# at2313_isp_adapter.net
KiCad netlist of a schematic drawn in EAGLE
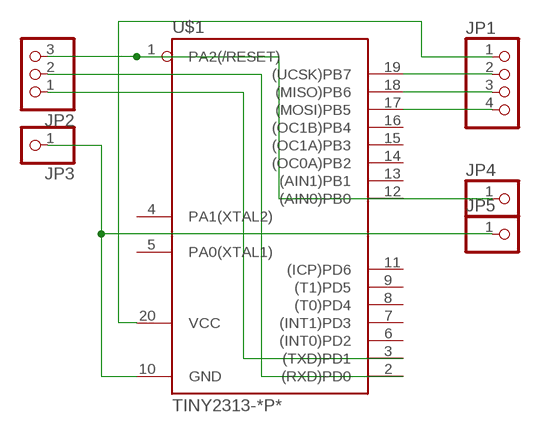
[diagram p0: schematic, sheet 1]

(export (version "E")
  (design (tool "Eeschema 10.0.6"))
  (components
    (comp (ref "JP1")
      (value "PINHD-1X4")
      (footprint "eagle-import:1X04")
      (libsource (lib "eagle-import") (part "PINHD-1X4"))
    )
    (comp (ref "JP2")
      (value "PINHD-1X3")
      (footprint "eagle-import:1X03")
      (libsource (lib "eagle-import") (part "PINHD-1X3"))
    )
    (comp (ref "JP3")
      (value "PINHD-1X1")
      (footprint "eagle-import:1X01")
      (libsource (lib "eagle-import") (part "PINHD-1X1"))
    )
    (comp (ref "JP4")
      (value "PINHD-1X1")
      (footprint "eagle-import:1X01")
      (libsource (lib "eagle-import") (part "PINHD-1X1"))
    )
    (comp (ref "JP5")
      (value "PINHD-1X1")
      (footprint "eagle-import:1X01")
      (libsource (lib "eagle-import") (part "PINHD-1X1"))
    )
    (comp (ref "U$1")
      (value "TINY2313-*P*")
      (footprint "eagle-import:DIL20")
      (libsource (lib "eagle-import") (part "TINY2313-P"))
    )
  )
  (nets
    (net (code "1") (name "Net-(U$1-(MISO)PB6)") (class "Default")
      (node (ref "JP1") (pin "3") (pinfunction "3_3") (pintype "passive"))
      (node (ref "U$1") (pin "18") (pinfunction "(MISO)PB6_18") (pintype "bidirectional"))
    )
    (net (code "2") (name "Net-(U$1-(MOSI)PB5)") (class "Default")
      (node (ref "JP1") (pin "4") (pinfunction "4_4") (pintype "passive"))
      (node (ref "U$1") (pin "17") (pinfunction "(MOSI)PB5_17") (pintype "bidirectional"))
    )
    (net (code "3") (name "Net-(U$1-(RXD)PD0)") (class "Default")
      (node (ref "JP2") (pin "2") (pinfunction "2_2") (pintype "passive"))
      (node (ref "U$1") (pin "2") (pinfunction "(RXD)PD0_2") (pintype "bidirectional"))
    )
    (net (code "4") (name "Net-(U$1-(TXD)PD1)") (class "Default")
      (node (ref "JP2") (pin "1") (pinfunction "1_1") (pintype "passive"))
      (node (ref "U$1") (pin "3") (pinfunction "(TXD)PD1_3") (pintype "bidirectional"))
    )
    (net (code "5") (name "Net-(U$1-(UCSK)PB7)") (class "Default")
      (node (ref "JP1") (pin "2") (pinfunction "2_2") (pintype "passive"))
      (node (ref "U$1") (pin "19") (pinfunction "(UCSK)PB7_19") (pintype "bidirectional"))
    )
    (net (code "6") (name "Net-(U$1-GND)") (class "Default")
      (node (ref "JP3") (pin "1") (pinfunction "1_1") (pintype "passive"))
      (node (ref "JP5") (pin "1") (pinfunction "1_1") (pintype "passive"))
      (node (ref "U$1") (pin "10") (pinfunction "GND_10") (pintype "power_in"))
    )
    (net (code "7") (name "Net-(U$1-PA2({slash}RESET))") (class "Default")
      (node (ref "JP2") (pin "3") (pinfunction "3_3") (pintype "passive"))
      (node (ref "JP4") (pin "1") (pinfunction "1_1") (pintype "passive"))
      (node (ref "U$1") (pin "1") (pinfunction "PA2(/RESET)_1") (pintype "input"))
    )
    (net (code "8") (name "Net-(U$1-VCC)") (class "Default")
      (node (ref "JP1") (pin "1") (pinfunction "1_1") (pintype "passive"))
      (node (ref "U$1") (pin "20") (pinfunction "VCC_20") (pintype "power_in"))
    )
    (net (code "9") (name "unconnected-(U$1-(AIN0)PB0-Pad12)") (class "Default")
      (node (ref "U$1") (pin "12") (pinfunction "(AIN0)PB0_12") (pintype "bidirectional"))
    )
    (net (code "10") (name "unconnected-(U$1-(AIN1)PB1-Pad13)") (class "Default")
      (node (ref "U$1") (pin "13") (pinfunction "(AIN1)PB1_13") (pintype "bidirectional"))
    )
    (net (code "11") (name "unconnected-(U$1-(ICP)PD6-Pad11)") (class "Default")
      (node (ref "U$1") (pin "11") (pinfunction "(ICP)PD6_11") (pintype "bidirectional"))
    )
    (net (code "12") (name "unconnected-(U$1-(INT0)PD2-Pad6)") (class "Default")
      (node (ref "U$1") (pin "6") (pinfunction "(INT0)PD2_6") (pintype "bidirectional"))
    )
    (net (code "13") (name "unconnected-(U$1-(INT1)PD3-Pad7)") (class "Default")
      (node (ref "U$1") (pin "7") (pinfunction "(INT1)PD3_7") (pintype "bidirectional"))
    )
    (net (code "14") (name "unconnected-(U$1-(OC0A)PB2-Pad14)") (class "Default")
      (node (ref "U$1") (pin "14") (pinfunction "(OC0A)PB2_14") (pintype "bidirectional"))
    )
    (net (code "15") (name "unconnected-(U$1-(OC1A)PB3-Pad15)") (class "Default")
      (node (ref "U$1") (pin "15") (pinfunction "(OC1A)PB3_15") (pintype "bidirectional"))
    )
    (net (code "16") (name "unconnected-(U$1-(OC1B)PB4-Pad16)") (class "Default")
      (node (ref "U$1") (pin "16") (pinfunction "(OC1B)PB4_16") (pintype "bidirectional"))
    )
    (net (code "17") (name "unconnected-(U$1-(T0)PD4-Pad8)") (class "Default")
      (node (ref "U$1") (pin "8") (pinfunction "(T0)PD4_8") (pintype "bidirectional"))
    )
    (net (code "18") (name "unconnected-(U$1-(T1)PD5-Pad9)") (class "Default")
      (node (ref "U$1") (pin "9") (pinfunction "(T1)PD5_9") (pintype "bidirectional"))
    )
    (net (code "19") (name "unconnected-(U$1-PA0(XTAL1)-Pad5)") (class "Default")
      (node (ref "U$1") (pin "5") (pinfunction "PA0(XTAL1)_5") (pintype "bidirectional"))
    )
    (net (code "20") (name "unconnected-(U$1-PA1(XTAL2)-Pad4)") (class "Default")
      (node (ref "U$1") (pin "4") (pinfunction "PA1(XTAL2)_4") (pintype "bidirectional"))
    )
  )
)
